# WiFi_ESP-12E.net
KiCad netlist of a schematic drawn in Altium Designer
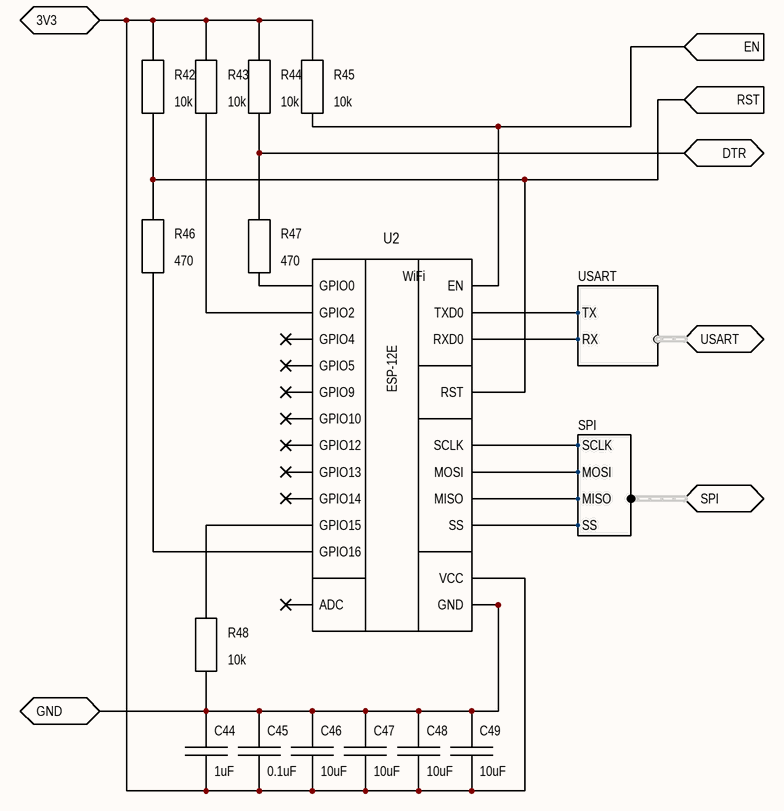
[diagram p0: WiFi ESP-12E.SchDoc]

(export (version "E")
  (design (tool "Eeschema 10.0.6"))
  (components
    (comp (ref "C44")
      (value "1uF")
      (footprint "CAPC1608M")
      (description "1uF 10V 0603(1608)")
      (fields (field (name "TOLERANCE") "±10%") (field (name "MANUFACTURER") "Yageo"))
      (libsource (lib "Capacitors Ceramic") (part "CC0603KRX5R6BB105"))
    )
    (comp (ref "C45")
      (value "0.1uF")
      (footprint "CAPC1608M")
      (description "0.1uF 16V 0603(1608)")
      (fields (field (name "TOLERANCE") "±10%") (field (name "MANUFACTURER") "Yageo"))
      (libsource (lib "Capacitors Ceramic") (part "CC0603KRX7R7BB104"))
    )
    (comp (ref "C46")
      (value "10uF")
      (footprint "CAPC2012M")
      (description "10uF 6.3V 0805(2012)")
      (fields (field (name "TOLERANCE") "±20%") (field (name "MANUFACTURER") "Yageo"))
      (libsource (lib "Capacitors Ceramic") (part "CC0805MRX5R5BB106"))
    )
    (comp (ref "C47")
      (value "10uF")
      (footprint "CAPC2012M")
      (description "10uF 6.3V 0805(2012)")
      (fields (field (name "TOLERANCE") "±20%") (field (name "MANUFACTURER") "Yageo"))
      (libsource (lib "Capacitors Ceramic") (part "CC0805MRX5R5BB106"))
    )
    (comp (ref "C48")
      (value "10uF")
      (footprint "CAPC2012M")
      (description "10uF 6.3V 0805(2012)")
      (fields (field (name "TOLERANCE") "±20%") (field (name "MANUFACTURER") "Yageo"))
      (libsource (lib "Capacitors Ceramic") (part "CC0805MRX5R5BB106"))
    )
    (comp (ref "C49")
      (value "10uF")
      (footprint "CAPC2012M")
      (description "10uF 6.3V 0805(2012)")
      (fields (field (name "TOLERANCE") "±20%") (field (name "MANUFACTURER") "Yageo"))
      (libsource (lib "Capacitors Ceramic") (part "CC0805MRX5R5BB106"))
    )
    (comp (ref "R42")
      (value "10k")
      (footprint "RESC1608M")
      (description "10k 0603(1608)")
      (fields (field (name "MANUFACTURER") "Yageo") (field (name "TOLERANCE") "±5%"))
      (libsource (lib "Resistors Ceramic") (part "RC0603JR-0710KL"))
    )
    (comp (ref "R43")
      (value "10k")
      (footprint "RESC1608M")
      (description "10k 0603(1608)")
      (fields (field (name "MANUFACTURER") "Yageo") (field (name "TOLERANCE") "±5%"))
      (libsource (lib "Resistors Ceramic") (part "RC0603JR-0710KL"))
    )
    (comp (ref "R44")
      (value "10k")
      (footprint "RESC1608M")
      (description "10k 0603(1608)")
      (fields (field (name "MANUFACTURER") "Yageo") (field (name "TOLERANCE") "±5%"))
      (libsource (lib "Resistors Ceramic") (part "RC0603JR-0710KL"))
    )
    (comp (ref "R45")
      (value "10k")
      (footprint "RESC1608M")
      (description "10k 0603(1608)")
      (fields (field (name "MANUFACTURER") "Yageo") (field (name "TOLERANCE") "±5%"))
      (libsource (lib "Resistors Ceramic") (part "RC0603JR-0710KL"))
    )
    (comp (ref "R46")
      (value "470")
      (footprint "RESC1608M")
      (description "470 0603(1608)")
      (fields (field (name "MANUFACTURER") "Yageo") (field (name "TOLERANCE") "±5%"))
      (libsource (lib "Resistors Ceramic") (part "RC0603JR-07470RL"))
    )
    (comp (ref "R47")
      (value "470")
      (footprint "RESC1608M")
      (description "470 0603(1608)")
      (fields (field (name "MANUFACTURER") "Yageo") (field (name "TOLERANCE") "±5%"))
      (libsource (lib "Resistors Ceramic") (part "RC0603JR-07470RL"))
    )
    (comp (ref "R48")
      (value "10k")
      (footprint "RESC1608M")
      (description "10k 0603(1608)")
      (fields (field (name "MANUFACTURER") "Yageo") (field (name "TOLERANCE") "±5%"))
      (libsource (lib "Resistors Ceramic") (part "RC0603JR-0710KL"))
    )
    (comp (ref "U2")
      (value "ESP-12E")
      (footprint "ESP-12E")
      (description "WiFi Module based on ESP8266")
      (fields (field (name "MANUFACTURER") "Espressif"))
      (libsource (lib "RF Modules") (part "ESP-12E"))
    )
  )
  (nets
    (net (code "3") (name "/3V3") (class "Default")
      (node (ref "C44") (pin "2") (pinfunction "2_2") (pintype "passive"))
      (node (ref "C45") (pin "2") (pinfunction "2_2") (pintype "passive"))
      (node (ref "C46") (pin "2") (pinfunction "2_2") (pintype "passive"))
      (node (ref "C47") (pin "2") (pinfunction "2_2") (pintype "passive"))
      (node (ref "C48") (pin "2") (pinfunction "2_2") (pintype "passive"))
      (node (ref "C49") (pin "2") (pinfunction "2_2") (pintype "passive"))
      (node (ref "R42") (pin "1") (pinfunction "1_1") (pintype "passive"))
      (node (ref "R43") (pin "1") (pinfunction "1_1") (pintype "passive"))
      (node (ref "R44") (pin "1") (pinfunction "1_1") (pintype "passive"))
      (node (ref "R45") (pin "1") (pinfunction "1_1") (pintype "passive"))
      (node (ref "U2") (pin "VCC") (pinfunction "VCC_VCC") (pintype "passive"))
    )
    (net (code "4") (name "/DTR") (class "Default")
      (node (ref "R44") (pin "2") (pinfunction "2_2") (pintype "passive"))
      (node (ref "R47") (pin "1") (pinfunction "1_1") (pintype "passive"))
    )
    (net (code "5") (name "/EN") (class "Default")
      (node (ref "R45") (pin "2") (pinfunction "2_2") (pintype "passive"))
      (node (ref "U2") (pin "EN") (pinfunction "EN_EN") (pintype "passive"))
    )
    (net (code "6") (name "/GND") (class "Default")
      (node (ref "C44") (pin "1") (pinfunction "1_1") (pintype "passive"))
      (node (ref "C45") (pin "1") (pinfunction "1_1") (pintype "passive"))
      (node (ref "C46") (pin "1") (pinfunction "1_1") (pintype "passive"))
      (node (ref "C47") (pin "1") (pinfunction "1_1") (pintype "passive"))
      (node (ref "C48") (pin "1") (pinfunction "1_1") (pintype "passive"))
      (node (ref "C49") (pin "1") (pinfunction "1_1") (pintype "passive"))
      (node (ref "R48") (pin "2") (pinfunction "2_2") (pintype "passive"))
      (node (ref "U2") (pin "GND") (pinfunction "GND_GND") (pintype "passive"))
    )
    (net (code "7") (name "/MISO") (class "Default")
      (node (ref "U2") (pin "MISO") (pinfunction "MISO_MISO") (pintype "passive"))
    )
    (net (code "8") (name "/MOSI") (class "Default")
      (node (ref "U2") (pin "MOSI") (pinfunction "MOSI_MOSI") (pintype "passive"))
    )
    (net (code "9") (name "/RST") (class "Default")
      (node (ref "R42") (pin "2") (pinfunction "2_2") (pintype "passive"))
      (node (ref "R46") (pin "1") (pinfunction "1_1") (pintype "passive"))
      (node (ref "U2") (pin "RST") (pinfunction "RST_RST") (pintype "passive"))
    )
    (net (code "10") (name "/RX") (class "Default")
      (node (ref "U2") (pin "RXD0") (pinfunction "RXD0_RXD0") (pintype "passive"))
    )
    (net (code "11") (name "/SCLK") (class "Default")
      (node (ref "U2") (pin "SCLK") (pinfunction "SCLK_SCLK") (pintype "passive"))
    )
    (net (code "12") (name "/SS") (class "Default")
      (node (ref "U2") (pin "CS0") (pinfunction "SS_CS0") (pintype "passive"))
    )
    (net (code "13") (name "/TX") (class "Default")
      (node (ref "U2") (pin "TXD0") (pinfunction "TXD0_TXD0") (pintype "passive"))
    )
    (net (code "16") (name "Net-(R43-Pad2)") (class "Default")
      (node (ref "R43") (pin "2") (pinfunction "2_2") (pintype "passive"))
      (node (ref "U2") (pin "GPIO2") (pinfunction "GPIO2_GPIO2") (pintype "passive"))
    )
    (net (code "17") (name "Net-(R46-Pad2)") (class "Default")
      (node (ref "R46") (pin "2") (pinfunction "2_2") (pintype "passive"))
      (node (ref "U2") (pin "GPIO16") (pinfunction "GPIO16_GPIO16") (pintype "passive"))
    )
    (net (code "18") (name "Net-(R47-Pad2)") (class "Default")
      (node (ref "R47") (pin "2") (pinfunction "2_2") (pintype "passive"))
      (node (ref "U2") (pin "GPIO0") (pinfunction "GPIO0_GPIO0") (pintype "passive"))
    )
    (net (code "19") (name "Net-(R48-Pad1)") (class "Default")
      (node (ref "R48") (pin "1") (pinfunction "1_1") (pintype "passive"))
      (node (ref "U2") (pin "GPIO15") (pinfunction "GPIO15_GPIO15") (pintype "passive"))
    )
    (net (code "20") (name "unconnected-(U2-PadADC)") (class "Default")
      (node (ref "U2") (pin "ADC") (pinfunction "ADC_ADC") (pintype "passive+no_connect"))
    )
    (net (code "21") (name "unconnected-(U2-PadGPIO4)") (class "Default")
      (node (ref "U2") (pin "GPIO4") (pinfunction "GPIO4_GPIO4") (pintype "passive+no_connect"))
    )
    (net (code "22") (name "unconnected-(U2-PadGPIO5)") (class "Default")
      (node (ref "U2") (pin "GPIO5") (pinfunction "GPIO5_GPIO5") (pintype "passive+no_connect"))
    )
    (net (code "23") (name "unconnected-(U2-PadGPIO9)") (class "Default")
      (node (ref "U2") (pin "GPIO9") (pinfunction "GPIO9_GPIO9") (pintype "passive+no_connect"))
    )
    (net (code "24") (name "unconnected-(U2-PadGPIO10)") (class "Default")
      (node (ref "U2") (pin "GPIO10") (pinfunction "GPIO10_GPIO10") (pintype "passive+no_connect"))
    )
    (net (code "25") (name "unconnected-(U2-PadGPIO12)") (class "Default")
      (node (ref "U2") (pin "GPIO12") (pinfunction "GPIO12_GPIO12") (pintype "passive+no_connect"))
    )
    (net (code "26") (name "unconnected-(U2-PadGPIO13)") (class "Default")
      (node (ref "U2") (pin "GPIO13") (pinfunction "GPIO13_GPIO13") (pintype "passive+no_connect"))
    )
    (net (code "27") (name "unconnected-(U2-PadGPIO14)") (class "Default")
      (node (ref "U2") (pin "GPIO14") (pinfunction "GPIO14_GPIO14") (pintype "passive+no_connect"))
    )
  )
)
